# C_76p593.net
KiCad netlist of a schematic drawn in Altium Designer
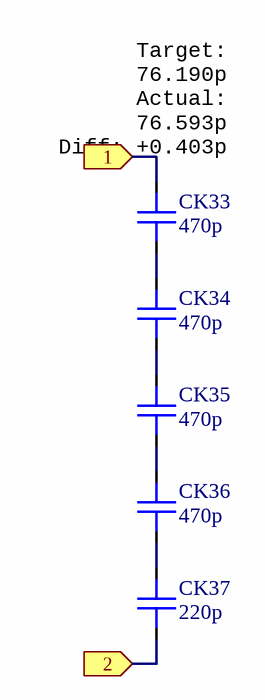
[diagram p0: C_76p593.SchDoc]

(export (version "E")
  (design (tool "Eeschema 10.0.6"))
  (components
    (comp (ref "CK33")
      (value "470p")
      (footprint "CAPC1005X06N(SMC0402)")
      (description "C; 470p; 50V; 1%; NP0/C0G; ??;")
      (fields (field (name "MANUFACTURER") "Kemet: C0402C471F5GAC7867;;Murata: GRM1555C1H471FA01D"))
      (libsource (lib "altium_sql") (part "CK"))
    )
    (comp (ref "CK34")
      (value "470p")
      (footprint "CAPC1005X06N(SMC0402)")
      (description "C; 470p; 50V; 1%; NP0/C0G; ??;")
      (fields (field (name "MANUFACTURER") "Kemet: C0402C471F5GAC7867;;Murata: GRM1555C1H471FA01D"))
      (libsource (lib "altium_sql") (part "CK"))
    )
    (comp (ref "CK35")
      (value "470p")
      (footprint "CAPC1005X06N(SMC0402)")
      (description "C; 470p; 50V; 1%; NP0/C0G; ??;")
      (fields (field (name "MANUFACTURER") "Kemet: C0402C471F5GAC7867;;Murata: GRM1555C1H471FA01D"))
      (libsource (lib "altium_sql") (part "CK"))
    )
    (comp (ref "CK36")
      (value "470p")
      (footprint "CAPC1005X06N(SMC0402)")
      (description "C; 470p; 50V; 1%; NP0/C0G; ??;")
      (fields (field (name "MANUFACTURER") "Kemet: C0402C471F5GAC7867;;Murata: GRM1555C1H471FA01D"))
      (libsource (lib "altium_sql") (part "CK"))
    )
    (comp (ref "CK37")
      (value "220p")
      (footprint "CAPC1005X06N(SMC0402)")
      (description "C; 220p; 50V; 1%; NP0/C0G; ??;")
      (fields (field (name "MANUFACTURER") "YAGEO: CC0402FRNPO9BN221"))
      (libsource (lib "altium_sql") (part "CK"))
    )
  )
  (nets
    (net (code "1") (name "/1") (class "Default")
      (node (ref "CK33") (pin "1") (pinfunction "1_1") (pintype "passive"))
    )
    (net (code "2") (name "/2") (class "Default")
      (node (ref "CK37") (pin "2") (pinfunction "2_2") (pintype "passive"))
    )
    (net (code "3") (name "Net-(CK33-Pad2)") (class "Default")
      (node (ref "CK33") (pin "2") (pinfunction "2_2") (pintype "passive"))
      (node (ref "CK34") (pin "1") (pinfunction "1_1") (pintype "passive"))
    )
    (net (code "4") (name "Net-(CK34-Pad2)") (class "Default")
      (node (ref "CK34") (pin "2") (pinfunction "2_2") (pintype "passive"))
      (node (ref "CK35") (pin "1") (pinfunction "1_1") (pintype "passive"))
    )
    (net (code "5") (name "Net-(CK35-Pad2)") (class "Default")
      (node (ref "CK35") (pin "2") (pinfunction "2_2") (pintype "passive"))
      (node (ref "CK36") (pin "1") (pinfunction "1_1") (pintype "passive"))
    )
    (net (code "6") (name "Net-(CK36-Pad2)") (class "Default")
      (node (ref "CK36") (pin "2") (pinfunction "2_2") (pintype "passive"))
      (node (ref "CK37") (pin "1") (pinfunction "1_1") (pintype "passive"))
    )
  )
)
